# power_board.net
KiCad netlist of a schematic drawn in EAGLE
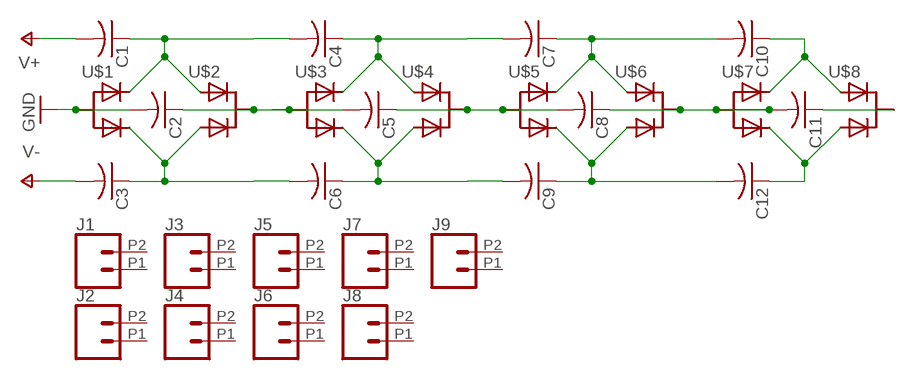
[diagram p0: schematic, sheet 1]

(export (version "E")
  (design (tool "Eeschema 10.0.6"))
  (components
    (comp (ref "C1")
      (value "C-USC1206")
      (footprint "eagle-import:C1206")
      (libsource (lib "eagle-import") (part "C-USC1206"))
    )
    (comp (ref "C2")
      (value "C-USC1206")
      (footprint "eagle-import:C1206")
      (libsource (lib "eagle-import") (part "C-USC1206"))
    )
    (comp (ref "C3")
      (value "C-USC1206")
      (footprint "eagle-import:C1206")
      (libsource (lib "eagle-import") (part "C-USC1206"))
    )
    (comp (ref "C4")
      (value "C-USC1206")
      (footprint "eagle-import:C1206")
      (libsource (lib "eagle-import") (part "C-USC1206"))
    )
    (comp (ref "C5")
      (value "C-USC1206")
      (footprint "eagle-import:C1206")
      (libsource (lib "eagle-import") (part "C-USC1206"))
    )
    (comp (ref "C6")
      (value "C-USC1206")
      (footprint "eagle-import:C1206")
      (libsource (lib "eagle-import") (part "C-USC1206"))
    )
    (comp (ref "C7")
      (value "C-USC1206")
      (footprint "eagle-import:C1206")
      (libsource (lib "eagle-import") (part "C-USC1206"))
    )
    (comp (ref "C8")
      (value "C-USC1206")
      (footprint "eagle-import:C1206")
      (libsource (lib "eagle-import") (part "C-USC1206"))
    )
    (comp (ref "C9")
      (value "C-USC1206")
      (footprint "eagle-import:C1206")
      (libsource (lib "eagle-import") (part "C-USC1206"))
    )
    (comp (ref "C10")
      (value "C-USC1206")
      (footprint "eagle-import:C1206")
      (libsource (lib "eagle-import") (part "C-USC1206"))
    )
    (comp (ref "C11")
      (value "C-USC1206")
      (footprint "eagle-import:C1206")
      (libsource (lib "eagle-import") (part "C-USC1206"))
    )
    (comp (ref "C12")
      (value "C-USC1206")
      (footprint "eagle-import:C1206")
      (libsource (lib "eagle-import") (part "C-USC1206"))
    )
    (comp (ref "J1")
      (value "CONN_022.54MM_SCREWTERM")
      (footprint "eagle-import:1X02_2.54_SCREWTERM")
      (libsource (lib "eagle-import") (part "CONN_022.54MM_SCREWTERM"))
    )
    (comp (ref "J2")
      (value "CONN_022.54MM_SCREWTERM")
      (footprint "eagle-import:1X02_2.54_SCREWTERM")
      (libsource (lib "eagle-import") (part "CONN_022.54MM_SCREWTERM"))
    )
    (comp (ref "J3")
      (value "CONN_022.54MM_SCREWTERM")
      (footprint "eagle-import:1X02_2.54_SCREWTERM")
      (libsource (lib "eagle-import") (part "CONN_022.54MM_SCREWTERM"))
    )
    (comp (ref "J4")
      (value "CONN_022.54MM_SCREWTERM")
      (footprint "eagle-import:1X02_2.54_SCREWTERM")
      (libsource (lib "eagle-import") (part "CONN_022.54MM_SCREWTERM"))
    )
    (comp (ref "J5")
      (value "CONN_022.54MM_SCREWTERM")
      (footprint "eagle-import:1X02_2.54_SCREWTERM")
      (libsource (lib "eagle-import") (part "CONN_022.54MM_SCREWTERM"))
    )
    (comp (ref "J6")
      (value "CONN_022.54MM_SCREWTERM")
      (footprint "eagle-import:1X02_2.54_SCREWTERM")
      (libsource (lib "eagle-import") (part "CONN_022.54MM_SCREWTERM"))
    )
    (comp (ref "J7")
      (value "CONN_022.54MM_SCREWTERM")
      (footprint "eagle-import:1X02_2.54_SCREWTERM")
      (libsource (lib "eagle-import") (part "CONN_022.54MM_SCREWTERM"))
    )
    (comp (ref "J8")
      (value "CONN_022.54MM_SCREWTERM")
      (footprint "eagle-import:1X02_2.54_SCREWTERM")
      (libsource (lib "eagle-import") (part "CONN_022.54MM_SCREWTERM"))
    )
    (comp (ref "J9")
      (value "CONN_022.54MM_SCREWTERM")
      (footprint "eagle-import:1X02_2.54_SCREWTERM")
      (libsource (lib "eagle-import") (part "CONN_022.54MM_SCREWTERM"))
    )
    (comp (ref "U$1")
      (value "BAT54AT")
      (footprint "eagle-import:SOT23")
      (libsource (lib "eagle-import") (part "BAT54AT"))
    )
    (comp (ref "U$2")
      (value "BAT54CT")
      (footprint "eagle-import:SOT23")
      (libsource (lib "eagle-import") (part "BAT54CT"))
    )
    (comp (ref "U$3")
      (value "BAT54AT")
      (footprint "eagle-import:SOT23")
      (libsource (lib "eagle-import") (part "BAT54AT"))
    )
    (comp (ref "U$4")
      (value "BAT54CT")
      (footprint "eagle-import:SOT23")
      (libsource (lib "eagle-import") (part "BAT54CT"))
    )
    (comp (ref "U$5")
      (value "BAT54AT")
      (footprint "eagle-import:SOT23")
      (libsource (lib "eagle-import") (part "BAT54AT"))
    )
    (comp (ref "U$6")
      (value "BAT54CT")
      (footprint "eagle-import:SOT23")
      (libsource (lib "eagle-import") (part "BAT54CT"))
    )
    (comp (ref "U$7")
      (value "BAT54AT")
      (footprint "eagle-import:SOT23")
      (libsource (lib "eagle-import") (part "BAT54AT"))
    )
    (comp (ref "U$8")
      (value "BAT54CT")
      (footprint "eagle-import:SOT23")
      (libsource (lib "eagle-import") (part "BAT54CT"))
    )
  )
  (nets
    (net (code "1") (name "GND") (class "Default")
      (node (ref "C2") (pin "2") (pinfunction "2_2") (pintype "passive"))
      (node (ref "U$1") (pin "3") (pinfunction "A_3") (pintype "passive"))
    )
    (net (code "2") (name "Net-(U$1-K1)") (class "Default")
      (node (ref "C1") (pin "1") (pinfunction "1_1") (pintype "passive"))
      (node (ref "C4") (pin "2") (pinfunction "2_2") (pintype "passive"))
      (node (ref "U$1") (pin "2") (pinfunction "K1_2") (pintype "passive"))
      (node (ref "U$2") (pin "1") (pinfunction "A1_1") (pintype "passive"))
    )
    (net (code "3") (name "Net-(U$1-K2)") (class "Default")
      (node (ref "C3") (pin "1") (pinfunction "1_1") (pintype "passive"))
      (node (ref "C6") (pin "2") (pinfunction "2_2") (pintype "passive"))
      (node (ref "U$1") (pin "1") (pinfunction "K2_1") (pintype "passive"))
      (node (ref "U$2") (pin "2") (pinfunction "A2_2") (pintype "passive"))
    )
    (net (code "4") (name "Net-(U$2-K)") (class "Default")
      (node (ref "C2") (pin "1") (pinfunction "1_1") (pintype "passive"))
      (node (ref "C5") (pin "2") (pinfunction "2_2") (pintype "passive"))
      (node (ref "U$2") (pin "3") (pinfunction "K_3") (pintype "passive"))
      (node (ref "U$3") (pin "3") (pinfunction "A_3") (pintype "passive"))
    )
    (net (code "5") (name "Net-(U$3-K1)") (class "Default")
      (node (ref "C4") (pin "1") (pinfunction "1_1") (pintype "passive"))
      (node (ref "C7") (pin "2") (pinfunction "2_2") (pintype "passive"))
      (node (ref "U$3") (pin "2") (pinfunction "K1_2") (pintype "passive"))
      (node (ref "U$4") (pin "1") (pinfunction "A1_1") (pintype "passive"))
    )
    (net (code "6") (name "Net-(U$3-K2)") (class "Default")
      (node (ref "C6") (pin "1") (pinfunction "1_1") (pintype "passive"))
      (node (ref "C9") (pin "2") (pinfunction "2_2") (pintype "passive"))
      (node (ref "U$3") (pin "1") (pinfunction "K2_1") (pintype "passive"))
      (node (ref "U$4") (pin "2") (pinfunction "A2_2") (pintype "passive"))
    )
    (net (code "7") (name "Net-(U$4-K)") (class "Default")
      (node (ref "C5") (pin "1") (pinfunction "1_1") (pintype "passive"))
      (node (ref "C8") (pin "2") (pinfunction "2_2") (pintype "passive"))
      (node (ref "U$4") (pin "3") (pinfunction "K_3") (pintype "passive"))
      (node (ref "U$5") (pin "3") (pinfunction "A_3") (pintype "passive"))
    )
    (net (code "8") (name "Net-(U$5-K1)") (class "Default")
      (node (ref "C10") (pin "2") (pinfunction "2_2") (pintype "passive"))
      (node (ref "C7") (pin "1") (pinfunction "1_1") (pintype "passive"))
      (node (ref "U$5") (pin "2") (pinfunction "K1_2") (pintype "passive"))
      (node (ref "U$6") (pin "1") (pinfunction "A1_1") (pintype "passive"))
    )
    (net (code "9") (name "Net-(U$5-K2)") (class "Default")
      (node (ref "C12") (pin "2") (pinfunction "2_2") (pintype "passive"))
      (node (ref "C9") (pin "1") (pinfunction "1_1") (pintype "passive"))
      (node (ref "U$5") (pin "1") (pinfunction "K2_1") (pintype "passive"))
      (node (ref "U$6") (pin "2") (pinfunction "A2_2") (pintype "passive"))
    )
    (net (code "10") (name "Net-(U$6-K)") (class "Default")
      (node (ref "C11") (pin "2") (pinfunction "2_2") (pintype "passive"))
      (node (ref "C8") (pin "1") (pinfunction "1_1") (pintype "passive"))
      (node (ref "U$6") (pin "3") (pinfunction "K_3") (pintype "passive"))
      (node (ref "U$7") (pin "3") (pinfunction "A_3") (pintype "passive"))
    )
    (net (code "11") (name "Net-(U$7-K1)") (class "Default")
      (node (ref "C10") (pin "1") (pinfunction "1_1") (pintype "passive"))
      (node (ref "U$7") (pin "2") (pinfunction "K1_2") (pintype "passive"))
      (node (ref "U$8") (pin "1") (pinfunction "A1_1") (pintype "passive"))
    )
    (net (code "12") (name "Net-(U$7-K2)") (class "Default")
      (node (ref "C12") (pin "1") (pinfunction "1_1") (pintype "passive"))
      (node (ref "U$7") (pin "1") (pinfunction "K2_1") (pintype "passive"))
      (node (ref "U$8") (pin "2") (pinfunction "A2_2") (pintype "passive"))
    )
    (net (code "13") (name "Net-(U$8-K)") (class "Default")
      (node (ref "C11") (pin "1") (pinfunction "1_1") (pintype "passive"))
      (node (ref "U$8") (pin "3") (pinfunction "K_3") (pintype "passive"))
    )
    (net (code "14") (name "V+") (class "Default")
      (node (ref "C1") (pin "2") (pinfunction "2_2") (pintype "passive"))
    )
    (net (code "15") (name "V-") (class "Default")
      (node (ref "C3") (pin "2") (pinfunction "2_2") (pintype "passive"))
    )
    (net (code "16") (name "unconnected-(J1-1-PadP1)") (class "Default")
      (node (ref "J1") (pin "P1") (pinfunction "1_P1") (pintype "passive"))
    )
    (net (code "17") (name "unconnected-(J1-2-PadP2)") (class "Default")
      (node (ref "J1") (pin "P2") (pinfunction "2_P2") (pintype "passive"))
    )
    (net (code "18") (name "unconnected-(J2-1-PadP1)") (class "Default")
      (node (ref "J2") (pin "P1") (pinfunction "1_P1") (pintype "passive"))
    )
    (net (code "19") (name "unconnected-(J2-2-PadP2)") (class "Default")
      (node (ref "J2") (pin "P2") (pinfunction "2_P2") (pintype "passive"))
    )
    (net (code "20") (name "unconnected-(J3-1-PadP1)") (class "Default")
      (node (ref "J3") (pin "P1") (pinfunction "1_P1") (pintype "passive"))
    )
    (net (code "21") (name "unconnected-(J3-2-PadP2)") (class "Default")
      (node (ref "J3") (pin "P2") (pinfunction "2_P2") (pintype "passive"))
    )
    (net (code "22") (name "unconnected-(J4-1-PadP1)") (class "Default")
      (node (ref "J4") (pin "P1") (pinfunction "1_P1") (pintype "passive"))
    )
    (net (code "23") (name "unconnected-(J4-2-PadP2)") (class "Default")
      (node (ref "J4") (pin "P2") (pinfunction "2_P2") (pintype "passive"))
    )
    (net (code "24") (name "unconnected-(J5-1-PadP1)") (class "Default")
      (node (ref "J5") (pin "P1") (pinfunction "1_P1") (pintype "passive"))
    )
    (net (code "25") (name "unconnected-(J5-2-PadP2)") (class "Default")
      (node (ref "J5") (pin "P2") (pinfunction "2_P2") (pintype "passive"))
    )
    (net (code "26") (name "unconnected-(J6-1-PadP1)") (class "Default")
      (node (ref "J6") (pin "P1") (pinfunction "1_P1") (pintype "passive"))
    )
    (net (code "27") (name "unconnected-(J6-2-PadP2)") (class "Default")
      (node (ref "J6") (pin "P2") (pinfunction "2_P2") (pintype "passive"))
    )
    (net (code "28") (name "unconnected-(J7-1-PadP1)") (class "Default")
      (node (ref "J7") (pin "P1") (pinfunction "1_P1") (pintype "passive"))
    )
    (net (code "29") (name "unconnected-(J7-2-PadP2)") (class "Default")
      (node (ref "J7") (pin "P2") (pinfunction "2_P2") (pintype "passive"))
    )
    (net (code "30") (name "unconnected-(J8-1-PadP1)") (class "Default")
      (node (ref "J8") (pin "P1") (pinfunction "1_P1") (pintype "passive"))
    )
    (net (code "31") (name "unconnected-(J8-2-PadP2)") (class "Default")
      (node (ref "J8") (pin "P2") (pinfunction "2_P2") (pintype "passive"))
    )
    (net (code "32") (name "unconnected-(J9-1-PadP1)") (class "Default")
      (node (ref "J9") (pin "P1") (pinfunction "1_P1") (pintype "passive"))
    )
    (net (code "33") (name "unconnected-(J9-2-PadP2)") (class "Default")
      (node (ref "J9") (pin "P2") (pinfunction "2_P2") (pintype "passive"))
    )
  )
)
